# transc_MIWI2400.net
KiCad netlist of a schematic drawn in Altium Designer
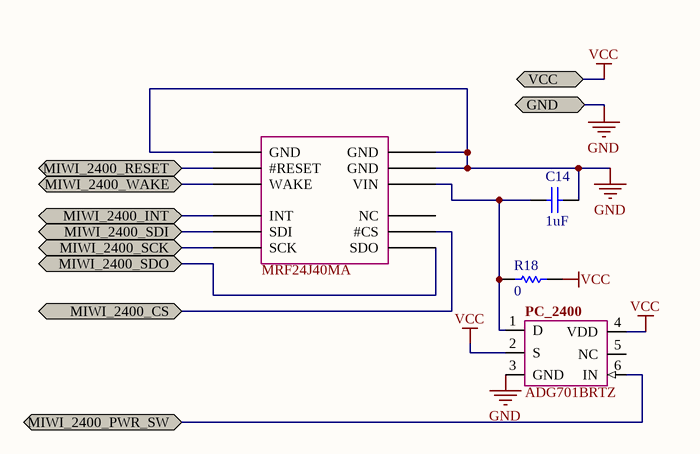
[diagram p0: transc_MIWI2400.SchDoc]

(export (version "E")
  (design (tool "Eeschema 10.0.6"))
  (components
    (comp (ref "C14")
      (value "1uF")
      (footprint "1608[0603]")
      (description "Capacitor")
      (fields (field (name "Comment") "Cap") (field (name "PUBLISHER") "Altium Limited"))
      (libsource (lib "Miscellaneous Devices") (part "Cap"))
    )
    (comp (ref "MRF24J40MA")
      (value "MRF24J40MA")
      (footprint "MRF24J40MA")
      (description "Microchip RF radio")
      (libsource (lib "agus_lib") (part "MRF24J40MA"))
    )
    (comp (ref "PC_2400")
      (value "ADG701BRTZ")
      (footprint "SOT23-6_L")
      (libsource (lib "PlacaBase_agus") (part "ADG701BRTZ"))
    )
    (comp (ref "R18")
      (value "0")
      (footprint "1608[0603]")
      (description "Resistor")
      (fields (field (name "Comment") "resistor") (field (name "PUBLISHER") "Altium Limited"))
      (libsource (lib "agus_lib") (part "RES"))
    )
  )
  (nets
    (net (code "1") (name "/MIWI_2400_CS") (class "Default")
      (node (ref "MRF24J40MA") (pin "8") (pinfunction "#CS_8") (pintype "passive"))
    )
    (net (code "2") (name "/MIWI_2400_INT") (class "Default")
      (node (ref "MRF24J40MA") (pin "4") (pinfunction "INT_4") (pintype "passive"))
    )
    (net (code "3") (name "/MIWI_2400_PWR_SW") (class "Default")
      (node (ref "PC_2400") (pin "6") (pinfunction "IN_6") (pintype "input"))
    )
    (net (code "4") (name "/MIWI_2400_RESET") (class "Default")
      (node (ref "MRF24J40MA") (pin "2") (pinfunction "#RESET_2") (pintype "passive"))
    )
    (net (code "5") (name "/MIWI_2400_SCK") (class "Default")
      (node (ref "MRF24J40MA") (pin "6") (pinfunction "SCK_6") (pintype "passive"))
    )
    (net (code "6") (name "/MIWI_2400_SDI") (class "Default")
      (node (ref "MRF24J40MA") (pin "5") (pinfunction "SDI_5") (pintype "passive"))
    )
    (net (code "7") (name "/MIWI_2400_SDO") (class "Default")
      (node (ref "MRF24J40MA") (pin "7") (pinfunction "SDO_7") (pintype "passive"))
    )
    (net (code "8") (name "/MIWI_2400_WAKE") (class "Default")
      (node (ref "MRF24J40MA") (pin "3") (pinfunction "WAKE_3") (pintype "passive"))
    )
    (net (code "9") (name "GND") (class "Default")
      (node (ref "C14") (pin "1") (pinfunction "1_1") (pintype "passive"))
      (node (ref "MRF24J40MA") (pin "1") (pinfunction "GND_1") (pintype "passive"))
      (node (ref "MRF24J40MA") (pin "11") (pinfunction "GND_11") (pintype "passive"))
      (node (ref "MRF24J40MA") (pin "12") (pinfunction "GND_12") (pintype "passive"))
      (node (ref "PC_2400") (pin "3") (pinfunction "GND_3") (pintype "passive"))
    )
    (net (code "10") (name "Net-(MRF24J40MA-VIN)") (class "Default")
      (node (ref "C14") (pin "2") (pinfunction "2_2") (pintype "passive"))
      (node (ref "MRF24J40MA") (pin "10") (pinfunction "VIN_10") (pintype "passive"))
      (node (ref "PC_2400") (pin "1") (pinfunction "D_1") (pintype "bidirectional"))
      (node (ref "R18") (pin "2") (pinfunction "2_2") (pintype "passive"))
    )
    (net (code "11") (name "VCC") (class "Default")
      (node (ref "PC_2400") (pin "2") (pinfunction "S_2") (pintype "bidirectional"))
      (node (ref "PC_2400") (pin "4") (pinfunction "VDD_4") (pintype "power_in"))
      (node (ref "R18") (pin "1") (pinfunction "1_1") (pintype "passive"))
    )
    (net (code "12") (name "unconnected-(MRF24J40MA-NC-Pad9)") (class "Default")
      (node (ref "MRF24J40MA") (pin "9") (pinfunction "NC_9") (pintype "passive"))
    )
    (net (code "13") (name "unconnected-(PC_2400-NC-Pad5)") (class "Default")
      (node (ref "PC_2400") (pin "5") (pinfunction "NC_5") (pintype "passive"))
    )
  )
)
